# Bleasy.net
KiCad netlist of a schematic drawn in EAGLE
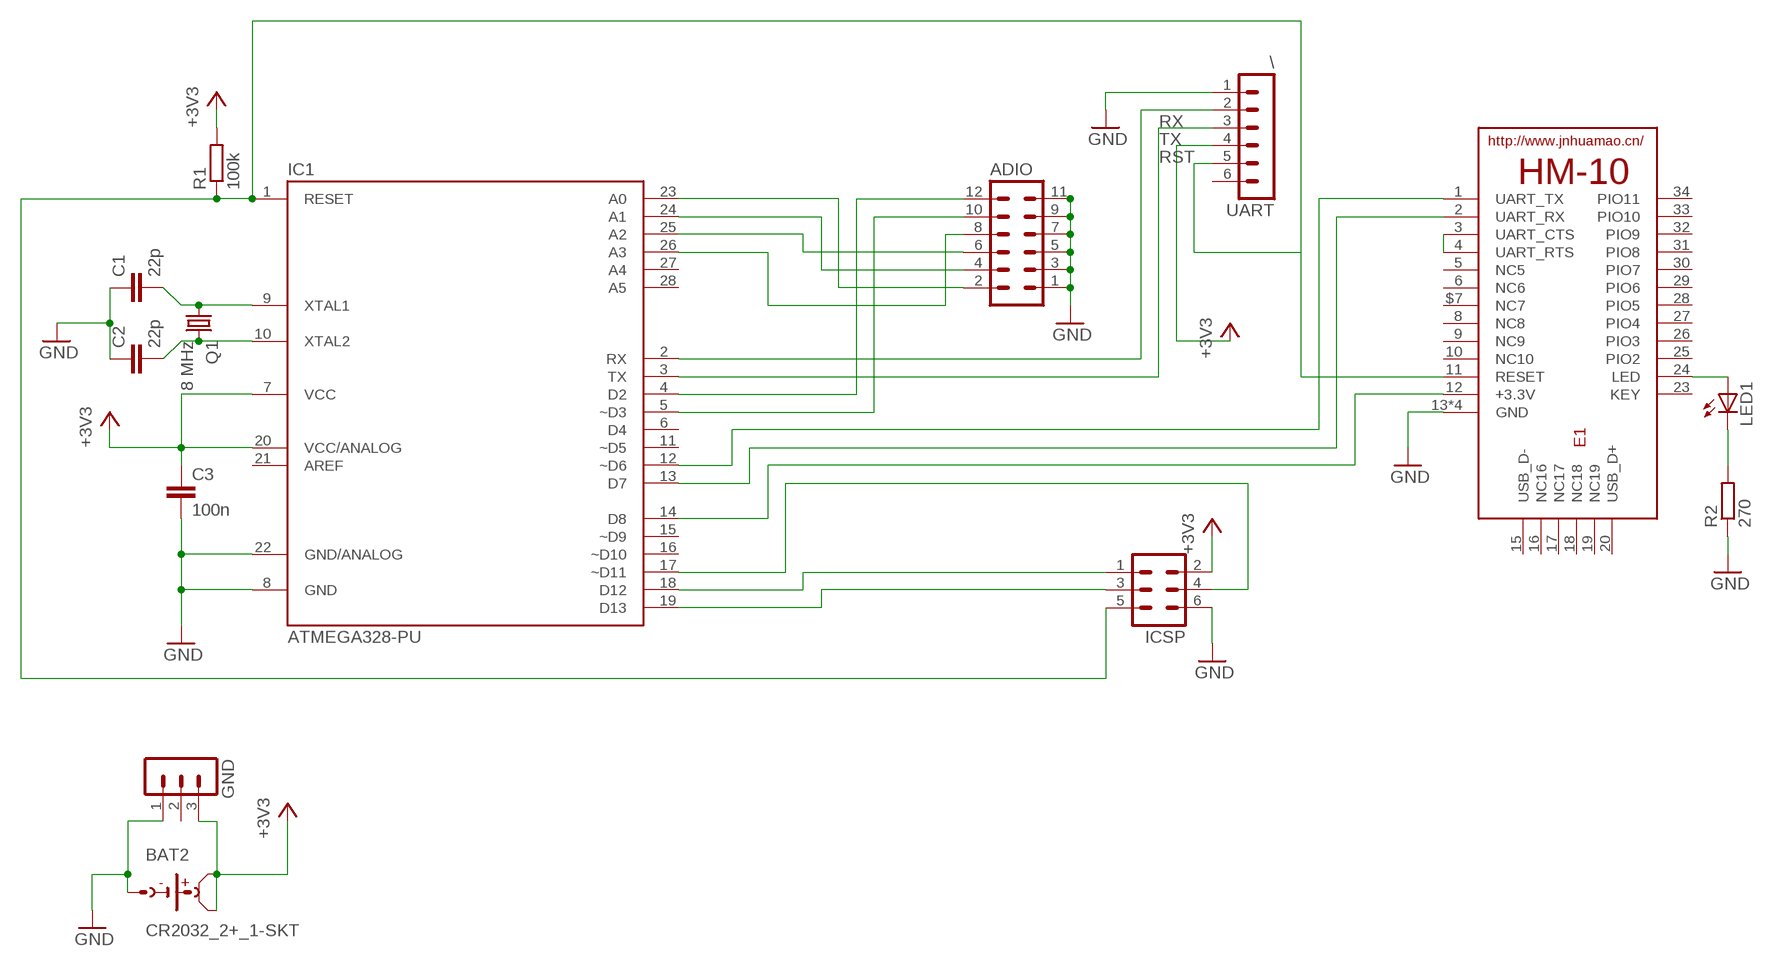
[diagram p0: schematic, sheet 1]

(export (version "E")
  (design (tool "Eeschema 10.0.6"))
  (components
    (comp (ref "ADIO")
      (value "MA06-2")
      (footprint "eagle-import:MA06-2")
      (libsource (lib "eagle-import") (part "MA06-2"))
    )
    (comp (ref "BAT2")
      (value "CR2032_2+_1-SKT")
      (footprint "eagle-import:CR2032-SOCKET-THT")
      (libsource (lib "eagle-import") (part "CR2032_2+_1-SKT"))
    )
    (comp (ref "C1")
      (value "22p")
      (footprint "eagle-import:C025-025X050")
      (libsource (lib "eagle-import") (part "C-EU025-025X050"))
    )
    (comp (ref "C2")
      (value "22p")
      (footprint "eagle-import:C025-025X050")
      (libsource (lib "eagle-import") (part "C-EU025-025X050"))
    )
    (comp (ref "C3")
      (value "100n")
      (footprint "eagle-import:C025-025X050")
      (libsource (lib "eagle-import") (part "C-EU025-025X050"))
    )
    (comp (ref "E1")
      (value "HM-10-BOARD")
      (footprint "eagle-import:26.9X13X2.2_BOARD")
      (libsource (lib "eagle-import") (part "HM-10-BOARD"))
    )
    (comp (ref "GND")
      (value "MA03-1")
      (footprint "eagle-import:MA03-1")
      (libsource (lib "eagle-import") (part "MA03-1"))
    )
    (comp (ref "IC1")
      (value "ATMEGA328-PU")
      (footprint "eagle-import:DIL28-3")
      (libsource (lib "eagle-import") (part "ATMEGA328-PU"))
    )
    (comp (ref "ICSP")
      (value "MA03-2")
      (footprint "eagle-import:MA03-2")
      (libsource (lib "eagle-import") (part "MA03-2"))
    )
    (comp (ref "LED1")
      (value "LED3MM")
      (footprint "eagle-import:LED3MM")
      (libsource (lib "eagle-import") (part "LED3MM"))
    )
    (comp (ref "Q1")
      (value "8 MHz")
      (footprint "eagle-import:HC49U70")
      (libsource (lib "eagle-import") (part "CRYSTALHC49U70"))
    )
    (comp (ref "R1")
      (value "100k")
      (footprint "eagle-import:R1206")
      (libsource (lib "eagle-import") (part "R-EU_R1206"))
    )
    (comp (ref "R2")
      (value "270")
      (footprint "eagle-import:R1206")
      (libsource (lib "eagle-import") (part "R-EU_R1206"))
    )
    (comp (ref "UART")
      (value "\\")
      (footprint "eagle-import:MA06-1")
      (libsource (lib "eagle-import") (part "MA06-1"))
    )
  )
  (nets
    (net (code "1") (name "+3V3") (class "Default")
      (node (ref "BAT2") (pin "2") (pinfunction "POS2_2") (pintype "power_in"))
      (node (ref "BAT2") (pin "3") (pinfunction "POS1_3") (pintype "power_in"))
      (node (ref "C3") (pin "1") (pinfunction "1_1") (pintype "passive"))
      (node (ref "GND") (pin "3") (pinfunction "3_3") (pintype "passive"))
      (node (ref "IC1") (pin "20") (pinfunction "VCC/ANALOG_20") (pintype "passive"))
      (node (ref "IC1") (pin "7") (pinfunction "VCC_7") (pintype "power_in"))
      (node (ref "ICSP") (pin "2") (pinfunction "2_2") (pintype "passive"))
      (node (ref "R1") (pin "2") (pinfunction "2_2") (pintype "passive"))
      (node (ref "UART") (pin "4") (pinfunction "4_4") (pintype "passive"))
    )
    (net (code "2") (name "/RST") (class "Default")
      (node (ref "E1") (pin "11") (pinfunction "RESET_11") (pintype "bidirectional"))
      (node (ref "IC1") (pin "1") (pinfunction "RESET_1") (pintype "bidirectional"))
      (node (ref "ICSP") (pin "5") (pinfunction "5_5") (pintype "passive"))
      (node (ref "R1") (pin "1") (pinfunction "1_1") (pintype "passive"))
      (node (ref "UART") (pin "5") (pinfunction "5_5") (pintype "passive"))
    )
    (net (code "3") (name "/RX") (class "Default")
      (node (ref "IC1") (pin "2") (pinfunction "RX_2") (pintype "bidirectional"))
      (node (ref "UART") (pin "2") (pinfunction "2_2") (pintype "passive"))
    )
    (net (code "4") (name "/TX") (class "Default")
      (node (ref "IC1") (pin "3") (pinfunction "TX_3") (pintype "bidirectional"))
      (node (ref "UART") (pin "3") (pinfunction "3_3") (pintype "passive"))
    )
    (net (code "5") (name "GND") (class "Default")
      (node (ref "ADIO") (pin "1") (pinfunction "1_1") (pintype "passive"))
      (node (ref "ADIO") (pin "11") (pinfunction "11_11") (pintype "passive"))
      (node (ref "ADIO") (pin "3") (pinfunction "3_3") (pintype "passive"))
      (node (ref "ADIO") (pin "5") (pinfunction "5_5") (pintype "passive"))
      (node (ref "ADIO") (pin "7") (pinfunction "7_7") (pintype "passive"))
      (node (ref "ADIO") (pin "9") (pinfunction "9_9") (pintype "passive"))
      (node (ref "BAT2") (pin "1") (pinfunction "NEG_1") (pintype "power_in"))
      (node (ref "C1") (pin "1") (pinfunction "1_1") (pintype "passive"))
      (node (ref "C2") (pin "1") (pinfunction "1_1") (pintype "passive"))
      (node (ref "C3") (pin "2") (pinfunction "2_2") (pintype "passive"))
      (node (ref "E1") (pin "13") (pinfunction "GND_13") (pintype "bidirectional"))
      (node (ref "E1") (pin "14") (pinfunction "GND_14") (pintype "bidirectional"))
      (node (ref "E1") (pin "21") (pinfunction "GND_21") (pintype "bidirectional"))
      (node (ref "E1") (pin "22") (pinfunction "GND_22") (pintype "bidirectional"))
      (node (ref "GND") (pin "1") (pinfunction "1_1") (pintype "passive"))
      (node (ref "IC1") (pin "22") (pinfunction "GND/ANALOG_22") (pintype "power_in"))
      (node (ref "IC1") (pin "8") (pinfunction "GND_8") (pintype "power_in"))
      (node (ref "ICSP") (pin "6") (pinfunction "6_6") (pintype "passive"))
      (node (ref "R2") (pin "1") (pinfunction "1_1") (pintype "passive"))
      (node (ref "UART") (pin "1") (pinfunction "1_1") (pintype "passive"))
    )
    (net (code "6") (name "Net-(E1-+3.3V)") (class "Default")
      (node (ref "E1") (pin "12") (pinfunction "+3.3V_12") (pintype "bidirectional"))
      (node (ref "IC1") (pin "14") (pinfunction "D8_14") (pintype "bidirectional"))
    )
    (net (code "7") (name "Net-(E1-LED)") (class "Default")
      (node (ref "E1") (pin "24") (pinfunction "LED_24") (pintype "bidirectional"))
      (node (ref "LED1") (pin "A") (pinfunction "A_A") (pintype "passive"))
    )
    (net (code "8") (name "Net-(E1-UART_CTS)") (class "Default")
      (node (ref "E1") (pin "3") (pinfunction "UART_CTS_3") (pintype "bidirectional"))
      (node (ref "E1") (pin "4") (pinfunction "UART_RTS_4") (pintype "bidirectional"))
    )
    (net (code "9") (name "Net-(E1-UART_RX)") (class "Default")
      (node (ref "E1") (pin "2") (pinfunction "UART_RX_2") (pintype "bidirectional"))
      (node (ref "IC1") (pin "13") (pinfunction "D7_13") (pintype "bidirectional"))
    )
    (net (code "10") (name "Net-(E1-UART_TX)") (class "Default")
      (node (ref "E1") (pin "1") (pinfunction "UART_TX_1") (pintype "bidirectional"))
      (node (ref "IC1") (pin "12") (pinfunction "~{D6}_12") (pintype "bidirectional"))
    )
    (net (code "11") (name "Net-(IC1-A0)") (class "Default")
      (node (ref "ADIO") (pin "2") (pinfunction "2_2") (pintype "passive"))
      (node (ref "IC1") (pin "23") (pinfunction "A0_23") (pintype "bidirectional"))
    )
    (net (code "12") (name "Net-(IC1-A1)") (class "Default")
      (node (ref "ADIO") (pin "4") (pinfunction "4_4") (pintype "passive"))
      (node (ref "IC1") (pin "24") (pinfunction "A1_24") (pintype "bidirectional"))
    )
    (net (code "13") (name "Net-(IC1-A2)") (class "Default")
      (node (ref "ADIO") (pin "6") (pinfunction "6_6") (pintype "passive"))
      (node (ref "IC1") (pin "25") (pinfunction "A2_25") (pintype "bidirectional"))
    )
    (net (code "14") (name "Net-(IC1-A3)") (class "Default")
      (node (ref "ADIO") (pin "8") (pinfunction "8_8") (pintype "passive"))
      (node (ref "IC1") (pin "26") (pinfunction "A3_26") (pintype "bidirectional"))
    )
    (net (code "15") (name "Net-(IC1-D2)") (class "Default")
      (node (ref "ADIO") (pin "12") (pinfunction "12_12") (pintype "passive"))
      (node (ref "IC1") (pin "4") (pinfunction "D2_4") (pintype "bidirectional"))
    )
    (net (code "16") (name "Net-(IC1-D12)") (class "Default")
      (node (ref "IC1") (pin "18") (pinfunction "D12_18") (pintype "bidirectional"))
      (node (ref "ICSP") (pin "1") (pinfunction "1_1") (pintype "passive"))
    )
    (net (code "17") (name "Net-(IC1-D13)") (class "Default")
      (node (ref "IC1") (pin "19") (pinfunction "D13_19") (pintype "bidirectional"))
      (node (ref "ICSP") (pin "3") (pinfunction "3_3") (pintype "passive"))
    )
    (net (code "18") (name "Net-(IC1-XTAL1)") (class "Default")
      (node (ref "C1") (pin "2") (pinfunction "2_2") (pintype "passive"))
      (node (ref "IC1") (pin "9") (pinfunction "XTAL1_9") (pintype "bidirectional"))
      (node (ref "Q1") (pin "1") (pinfunction "1_1") (pintype "passive"))
    )
    (net (code "19") (name "Net-(IC1-XTAL2)") (class "Default")
      (node (ref "C2") (pin "2") (pinfunction "2_2") (pintype "passive"))
      (node (ref "IC1") (pin "10") (pinfunction "XTAL2_10") (pintype "bidirectional"))
      (node (ref "Q1") (pin "2") (pinfunction "2_2") (pintype "passive"))
    )
    (net (code "20") (name "Net-(IC1-~{D3})") (class "Default")
      (node (ref "ADIO") (pin "10") (pinfunction "10_10") (pintype "passive"))
      (node (ref "IC1") (pin "5") (pinfunction "~{D3}_5") (pintype "bidirectional"))
    )
    (net (code "21") (name "Net-(IC1-~{D11})") (class "Default")
      (node (ref "IC1") (pin "17") (pinfunction "~{D11}_17") (pintype "bidirectional"))
      (node (ref "ICSP") (pin "4") (pinfunction "4_4") (pintype "passive"))
    )
    (net (code "22") (name "Net-(LED1-C)") (class "Default")
      (node (ref "LED1") (pin "K") (pinfunction "C_K") (pintype "passive"))
      (node (ref "R2") (pin "2") (pinfunction "2_2") (pintype "passive"))
    )
    (net (code "23") (name "unconnected-(E1-KEY-Pad23)") (class "Default")
      (node (ref "E1") (pin "23") (pinfunction "KEY_23") (pintype "bidirectional"))
    )
    (net (code "24") (name "unconnected-(E1-NC5-Pad5)") (class "Default")
      (node (ref "E1") (pin "5") (pinfunction "NC5_5") (pintype "bidirectional"))
    )
    (net (code "25") (name "unconnected-(E1-NC6-Pad6)") (class "Default")
      (node (ref "E1") (pin "6") (pinfunction "NC6_6") (pintype "bidirectional"))
    )
    (net (code "26") (name "unconnected-(E1-NC7-Pad$7)") (class "Default")
      (node (ref "E1") (pin "$7") (pinfunction "NC7_$7") (pintype "bidirectional"))
    )
    (net (code "27") (name "unconnected-(E1-NC8-Pad8)") (class "Default")
      (node (ref "E1") (pin "8") (pinfunction "NC8_8") (pintype "bidirectional"))
    )
    (net (code "28") (name "unconnected-(E1-NC9-Pad9)") (class "Default")
      (node (ref "E1") (pin "9") (pinfunction "NC9_9") (pintype "bidirectional"))
    )
    (net (code "29") (name "unconnected-(E1-NC10-Pad10)") (class "Default")
      (node (ref "E1") (pin "10") (pinfunction "NC10_10") (pintype "bidirectional"))
    )
    (net (code "30") (name "unconnected-(E1-NC16-Pad16)") (class "Default")
      (node (ref "E1") (pin "16") (pinfunction "NC16_16") (pintype "bidirectional"))
    )
    (net (code "31") (name "unconnected-(E1-NC17-Pad17)") (class "Default")
      (node (ref "E1") (pin "17") (pinfunction "NC17_17") (pintype "bidirectional"))
    )
    (net (code "32") (name "unconnected-(E1-NC18-Pad18)") (class "Default")
      (node (ref "E1") (pin "18") (pinfunction "NC18_18") (pintype "bidirectional"))
    )
    (net (code "33") (name "unconnected-(E1-NC19-Pad19)") (class "Default")
      (node (ref "E1") (pin "19") (pinfunction "NC19_19") (pintype "bidirectional"))
    )
    (net (code "34") (name "unconnected-(E1-PIO2-Pad25)") (class "Default")
      (node (ref "E1") (pin "25") (pinfunction "PIO2_25") (pintype "bidirectional"))
    )
    (net (code "35") (name "unconnected-(E1-PIO3-Pad26)") (class "Default")
      (node (ref "E1") (pin "26") (pinfunction "PIO3_26") (pintype "bidirectional"))
    )
    (net (code "36") (name "unconnected-(E1-PIO4-Pad27)") (class "Default")
      (node (ref "E1") (pin "27") (pinfunction "PIO4_27") (pintype "bidirectional"))
    )
    (net (code "37") (name "unconnected-(E1-PIO5-Pad28)") (class "Default")
      (node (ref "E1") (pin "28") (pinfunction "PIO5_28") (pintype "bidirectional"))
    )
    (net (code "38") (name "unconnected-(E1-PIO6-Pad29)") (class "Default")
      (node (ref "E1") (pin "29") (pinfunction "PIO6_29") (pintype "bidirectional"))
    )
    (net (code "39") (name "unconnected-(E1-PIO7-Pad30)") (class "Default")
      (node (ref "E1") (pin "30") (pinfunction "PIO7_30") (pintype "bidirectional"))
    )
    (net (code "40") (name "unconnected-(E1-PIO8-Pad31)") (class "Default")
      (node (ref "E1") (pin "31") (pinfunction "PIO8_31") (pintype "bidirectional"))
    )
    (net (code "41") (name "unconnected-(E1-PIO9-Pad32)") (class "Default")
      (node (ref "E1") (pin "32") (pinfunction "PIO9_32") (pintype "bidirectional"))
    )
    (net (code "42") (name "unconnected-(E1-PIO10-Pad33)") (class "Default")
      (node (ref "E1") (pin "33") (pinfunction "PIO10_33") (pintype "bidirectional"))
    )
    (net (code "43") (name "unconnected-(E1-PIO11-Pad34)") (class "Default")
      (node (ref "E1") (pin "34") (pinfunction "PIO11_34") (pintype "bidirectional"))
    )
    (net (code "44") (name "unconnected-(E1-USB_D+-Pad20)") (class "Default")
      (node (ref "E1") (pin "20") (pinfunction "USB_D+_20") (pintype "bidirectional"))
    )
    (net (code "45") (name "unconnected-(E1-USB_D--Pad15)") (class "Default")
      (node (ref "E1") (pin "15") (pinfunction "USB_D-_15") (pintype "bidirectional"))
    )
    (net (code "46") (name "unconnected-(GND-Pad2)") (class "Default")
      (node (ref "GND") (pin "2") (pinfunction "2_2") (pintype "passive"))
    )
    (net (code "47") (name "unconnected-(IC1-A4-Pad27)") (class "Default")
      (node (ref "IC1") (pin "27") (pinfunction "A4_27") (pintype "bidirectional"))
    )
    (net (code "48") (name "unconnected-(IC1-A5-Pad28)") (class "Default")
      (node (ref "IC1") (pin "28") (pinfunction "A5_28") (pintype "bidirectional"))
    )
    (net (code "49") (name "unconnected-(IC1-AREF-Pad21)") (class "Default")
      (node (ref "IC1") (pin "21") (pinfunction "AREF_21") (pintype "passive"))
    )
    (net (code "50") (name "unconnected-(IC1-D4-Pad6)") (class "Default")
      (node (ref "IC1") (pin "6") (pinfunction "D4_6") (pintype "bidirectional"))
    )
    (net (code "51") (name "unconnected-(IC1-~{D5}-Pad11)") (class "Default")
      (node (ref "IC1") (pin "11") (pinfunction "~{D5}_11") (pintype "bidirectional"))
    )
    (net (code "52") (name "unconnected-(IC1-~{D9}-Pad15)") (class "Default")
      (node (ref "IC1") (pin "15") (pinfunction "~{D9}_15") (pintype "bidirectional"))
    )
    (net (code "53") (name "unconnected-(IC1-~{D10}-Pad16)") (class "Default")
      (node (ref "IC1") (pin "16") (pinfunction "~{D10}_16") (pintype "bidirectional"))
    )
    (net (code "54") (name "unconnected-(UART-Pad6)") (class "Default")
      (node (ref "UART") (pin "6") (pinfunction "6_6") (pintype "passive"))
    )
  )
)
